# ELN1project.net
KiCad netlist of a schematic drawn in Altium Designer
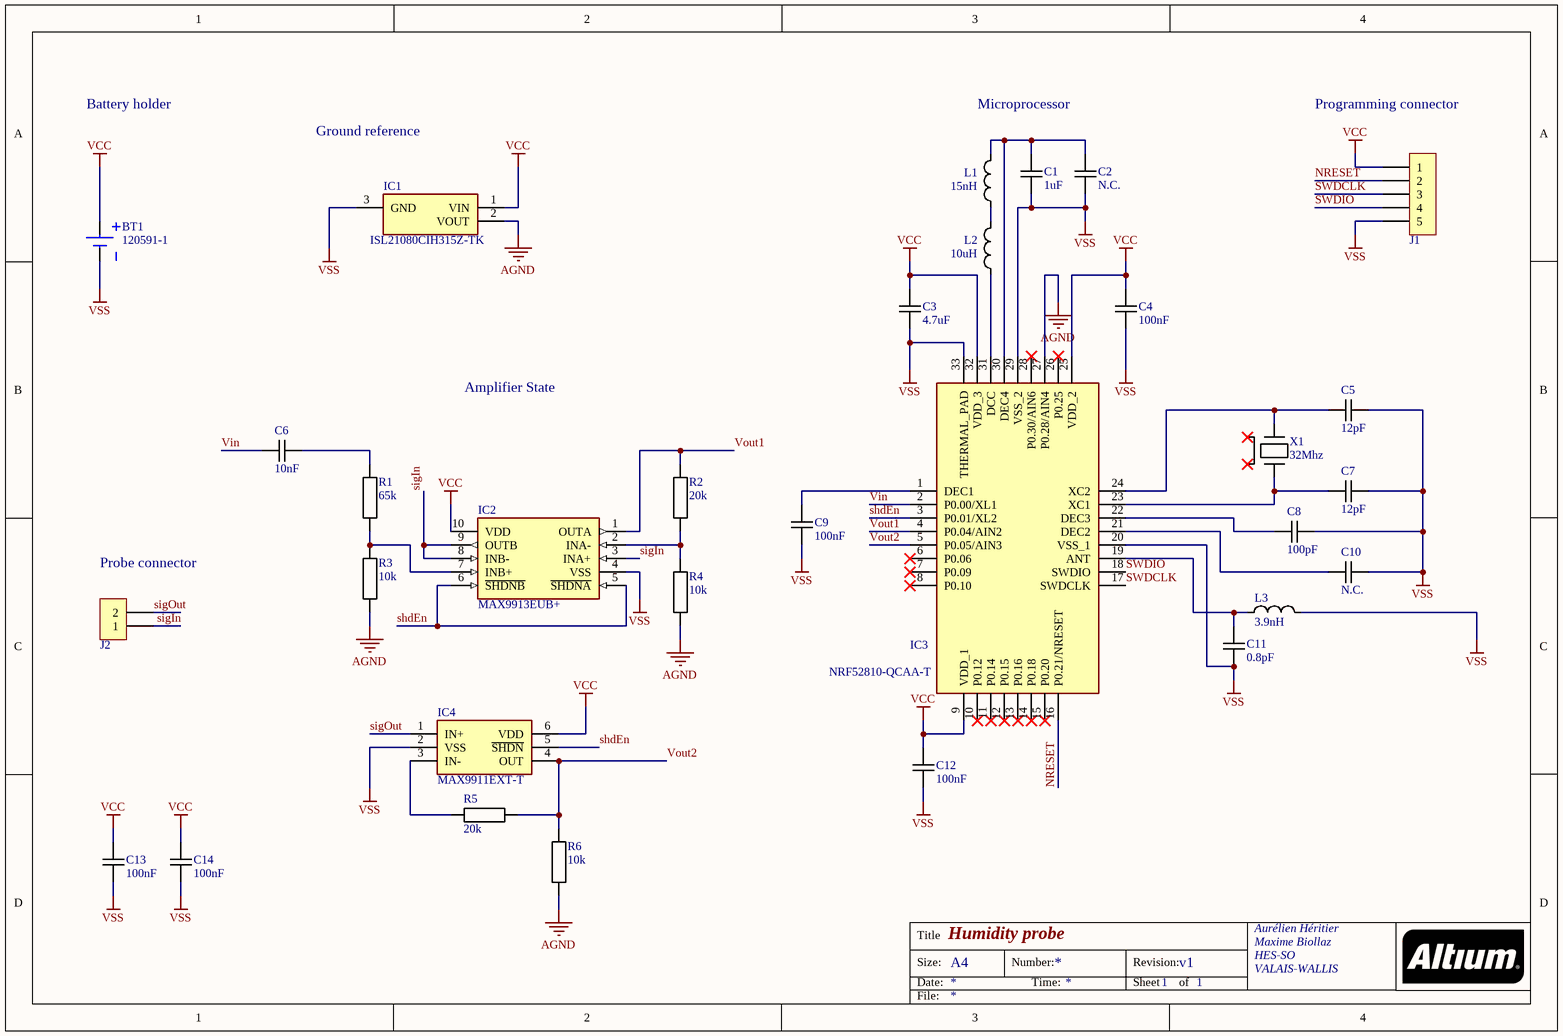
[diagram p0: ELN1project.SchDoc]

(export (version "E")
  (design (tool "Eeschema 10.0.6"))
  (components
    (comp (ref "BT1")
      (value "120591-1")
      (footprint "TECO-120591-1-2_V")
      (description "Lithium Battery Holder for CR2032 3V Cell")
      (fields (field (name "MANUFACTURER") "TE Connectivity"))
      (libsource (lib "TE_Connectivity_120591_1") (part "120591-1"))
    )
    (comp (ref "C1")
      (value "1uF")
      (footprint "CAPACITOR 1005 REFLOW")
      (description "Capacitor")
      (libsource (lib "altium-import") (part "root_1_Capacitor_"))
    )
    (comp (ref "C2")
      (value "N.C.")
      (footprint "CAPACITOR 1005 REFLOW")
      (description "Capacitor")
      (libsource (lib "altium-import") (part "root_1_Capacitor_"))
    )
    (comp (ref "C3")
      (value "4.7uF")
      (footprint "CAPACITOR 1005 REFLOW")
      (description "Capacitor")
      (libsource (lib "altium-import") (part "root_1_Capacitor_"))
    )
    (comp (ref "C4")
      (value "100nF")
      (footprint "CAPACITOR 1005 REFLOW")
      (description "Capacitor")
      (libsource (lib "altium-import") (part "root_1_Capacitor_"))
    )
    (comp (ref "C5")
      (value "12pF")
      (footprint "CAPACITOR 1005 REFLOW")
      (description "Capacitor")
      (libsource (lib "altium-import") (part "root_0_Capacitor_"))
    )
    (comp (ref "C6")
      (value "10nF")
      (footprint "CAPACITOR 1005 REFLOW")
      (description "Capacitor")
      (libsource (lib "altium-import") (part "root_2_Capacitor_"))
    )
    (comp (ref "C7")
      (value "12pF")
      (footprint "CAPACITOR 1005 REFLOW")
      (description "Capacitor")
      (libsource (lib "altium-import") (part "root_0_Capacitor_"))
    )
    (comp (ref "C8")
      (value "100pF")
      (footprint "CAPACITOR 1005 REFLOW")
      (description "Capacitor")
      (libsource (lib "altium-import") (part "root_0_Capacitor_"))
    )
    (comp (ref "C9")
      (value "100nF")
      (footprint "CAPACITOR 1005 REFLOW")
      (description "Capacitor")
      (libsource (lib "altium-import") (part "root_1_Capacitor_"))
    )
    (comp (ref "C10")
      (value "N.C.")
      (footprint "CAPACITOR 1005 REFLOW")
      (description "Capacitor")
      (libsource (lib "altium-import") (part "root_0_Capacitor_"))
    )
    (comp (ref "C11")
      (value "0.8pF")
      (footprint "CAPACITOR 1005 REFLOW")
      (description "Capacitor")
      (libsource (lib "altium-import") (part "root_1_Capacitor_"))
    )
    (comp (ref "C12")
      (value "100nF")
      (footprint "CAPACITOR 1005 REFLOW")
      (description "Capacitor")
      (libsource (lib "altium-import") (part "root_1_Capacitor_"))
    )
    (comp (ref "C13")
      (value "100nF")
      (footprint "CAPACITOR 1005 REFLOW")
      (description "Capacitor")
      (libsource (lib "altium-import") (part "root_1_Capacitor_"))
    )
    (comp (ref "C14")
      (value "100nF")
      (footprint "CAPACITOR 1005 REFLOW")
      (description "Capacitor")
      (libsource (lib "altium-import") (part "root_1_Capacitor_"))
    )
    (comp (ref "IC1")
      (value "ISL21080CIH315Z-TK")
      (footprint "SamacSys:SOT95P237X112-3N")
      (description "Integrated Circuit")
      (fields (field (name "MOUSER PART NUMBER") "968-ISL21080CIH315ZT"))
      (libsource (lib "*") (part "ISL21080CIH315Z-TK"))
    )
    (comp (ref "IC2")
      (value "MAX9913EUB+")
      (footprint "SamacSys:SOP50P490X110-10N")
      (description "Integrated Circuit")
      (libsource (lib "*") (part "MAX9913EUB+"))
    )
    (comp (ref "IC3")
      (value "NRF52810-QCAA-T")
      (footprint "SamacSys:QFN50P500X500X80-33N")
      (description "Integrated Circuit")
      (fields
        (field (name "MOUSER PART NUMBER") "949-NRF52810-QCAA-T")
        (field (name "RS PART NUMBER") "1697120P")
      )
      (libsource (lib "*") (part "NRF52810-QCAA-T"))
    )
    (comp (ref "IC4")
      (value "MAX9911EXT-T")
      (footprint "SamacSys:SOT65P218X110-6N")
      (description "Integrated Circuit")
      (libsource (lib "*") (part "MAX9911EXT-T"))
    )
    (comp (ref "J1")
      (value "*")
      (footprint "PinHeader1x5 P1.27")
      (description "Plug connector")
      (libsource (lib "PinHeader") (part "PinHeader1x5"))
    )
    (comp (ref "J2")
      (value "*")
      (footprint "PinHeader1x2 P1.27")
      (description "Plug connector")
      (libsource (lib "altium-import") (part "root_2_PinHeader1x2_"))
    )
    (comp (ref "L1")
      (value "15nH")
      (footprint "INDUCTOR 1005 REFLOW")
      (description "Inductor")
      (libsource (lib "altium-import") (part "root_1_Inductor_"))
    )
    (comp (ref "L2")
      (value "10uH")
      (footprint "INDUCTOR 1005 REFLOW")
      (description "Inductor")
      (libsource (lib "altium-import") (part "root_1_Inductor_"))
    )
    (comp (ref "L3")
      (value "3.9nH")
      (footprint "INDUCTOR 1005 REFLOW")
      (description "Inductor")
      (libsource (lib "altium-import") (part "root_0_Inductor_"))
    )
    (comp (ref "R1")
      (value "65k")
      (footprint "RESISTOR 0603 REFLOW")
      (description "Resistor")
      (libsource (lib "altium-import") (part "root_1_Resistor_"))
    )
    (comp (ref "R2")
      (value "20k")
      (footprint "RESISTOR 0603 REFLOW")
      (description "Resistor")
      (libsource (lib "altium-import") (part "root_1_Resistor_"))
    )
    (comp (ref "R3")
      (value "10k")
      (footprint "RESISTOR 0603 REFLOW")
      (description "Resistor")
      (libsource (lib "altium-import") (part "root_1_Resistor_"))
    )
    (comp (ref "R4")
      (value "10k")
      (footprint "RESISTOR 0603 REFLOW")
      (description "Resistor")
      (libsource (lib "altium-import") (part "root_1_Resistor_"))
    )
    (comp (ref "R5")
      (value "20k")
      (footprint "RESISTOR 0603 REFLOW")
      (description "Resistor")
      (libsource (lib "altium-import") (part "root_2_Resistor_"))
    )
    (comp (ref "R6")
      (value "10k")
      (footprint "RESISTOR 0603 REFLOW")
      (description "Resistor")
      (libsource (lib "altium-import") (part "root_3_Resistor_"))
    )
    (comp (ref "X1")
      (value "32Mhz")
      (footprint "Crystal C2.0x1.6 Abracon ABM11W")
      (description "Crystal C2.0x1.6 Abracon ABM11W")
      (libsource (lib "altium-import") (part "root_3_Crystal C2.0x1.6 Abracon ABM11W_"))
    )
  )
  (nets
    (net (code "1") (name "/NRESET") (class "Default")
      (node (ref "IC3") (pin "16") (pinfunction "P0.21/NRESET_16") (pintype "passive"))
      (node (ref "J1") (pin "2") (pinfunction "2_2") (pintype "passive"))
    )
    (net (code "2") (name "/SWDCLK") (class "Default")
      (node (ref "IC3") (pin "17") (pinfunction "SWDCLK_17") (pintype "passive"))
      (node (ref "J1") (pin "3") (pinfunction "3_3") (pintype "passive"))
    )
    (net (code "3") (name "/SWDIO") (class "Default")
      (node (ref "IC3") (pin "18") (pinfunction "SWDIO_18") (pintype "passive"))
      (node (ref "J1") (pin "4") (pinfunction "4_4") (pintype "passive"))
    )
    (net (code "4") (name "/Vin") (class "Default")
      (node (ref "C6") (pin "2") (pinfunction "2_2") (pintype "passive"))
      (node (ref "IC3") (pin "2") (pinfunction "P0.00/XL1_2") (pintype "passive"))
    )
    (net (code "5") (name "/Vout1") (class "Default")
      (node (ref "IC2") (pin "1") (pinfunction "OUTA_1") (pintype "output"))
      (node (ref "IC3") (pin "4") (pinfunction "P0.04/AIN2_4") (pintype "passive"))
      (node (ref "R2") (pin "2") (pinfunction "2_2") (pintype "passive"))
    )
    (net (code "6") (name "/Vout2") (class "Default")
      (node (ref "IC3") (pin "5") (pinfunction "P0.05/AIN3_5") (pintype "passive"))
      (node (ref "IC4") (pin "4") (pinfunction "OUT_4") (pintype "passive"))
      (node (ref "R5") (pin "1") (pinfunction "1_1") (pintype "passive"))
      (node (ref "R6") (pin "1") (pinfunction "1_1") (pintype "passive"))
    )
    (net (code "7") (name "/shdEn") (class "Default")
      (node (ref "IC2") (pin "5") (pinfunction "~{SHDNA}_5") (pintype "input"))
      (node (ref "IC2") (pin "6") (pinfunction "~{SHDNB}_6") (pintype "input"))
      (node (ref "IC3") (pin "3") (pinfunction "P0.01/XL2_3") (pintype "passive"))
      (node (ref "IC4") (pin "5") (pinfunction "~{SHDN}_5") (pintype "passive"))
    )
    (net (code "8") (name "/sigIn") (class "Default")
      (node (ref "IC2") (pin "3") (pinfunction "INA+_3") (pintype "input"))
      (node (ref "IC2") (pin "8") (pinfunction "INB-_8") (pintype "input"))
      (node (ref "IC2") (pin "9") (pinfunction "OUTB_9") (pintype "output"))
      (node (ref "J2") (pin "1") (pinfunction "1_1") (pintype "passive"))
    )
    (net (code "9") (name "/sigOut") (class "Default")
      (node (ref "IC4") (pin "1") (pinfunction "IN+_1") (pintype "passive"))
      (node (ref "J2") (pin "2") (pinfunction "2_2") (pintype "passive"))
    )
    (net (code "10") (name "AGND") (class "Default")
      (node (ref "IC1") (pin "2") (pinfunction "VOUT_2") (pintype "passive"))
      (node (ref "IC3") (pin "27") (pinfunction "P0.28/AIN4_27") (pintype "passive"))
      (node (ref "R3") (pin "1") (pinfunction "1_1") (pintype "passive"))
      (node (ref "R4") (pin "1") (pinfunction "1_1") (pintype "passive"))
      (node (ref "R6") (pin "2") (pinfunction "2_2") (pintype "passive"))
    )
    (net (code "11") (name "Net-(C6-Pad1)") (class "Default")
      (node (ref "C6") (pin "1") (pinfunction "1_1") (pintype "passive"))
      (node (ref "R1") (pin "2") (pinfunction "2_2") (pintype "passive"))
    )
    (net (code "12") (name "Net-(IC2-INA-)") (class "Default")
      (node (ref "IC2") (pin "2") (pinfunction "INA-_2") (pintype "input"))
      (node (ref "R2") (pin "1") (pinfunction "1_1") (pintype "passive"))
      (node (ref "R4") (pin "2") (pinfunction "2_2") (pintype "passive"))
    )
    (net (code "13") (name "Net-(IC2-INB+)") (class "Default")
      (node (ref "IC2") (pin "7") (pinfunction "INB+_7") (pintype "input"))
      (node (ref "R1") (pin "1") (pinfunction "1_1") (pintype "passive"))
      (node (ref "R3") (pin "2") (pinfunction "2_2") (pintype "passive"))
    )
    (net (code "14") (name "Net-(IC3-ANT)") (class "Default")
      (node (ref "C11") (pin "2") (pinfunction "2_2") (pintype "passive"))
      (node (ref "IC3") (pin "19") (pinfunction "ANT_19") (pintype "passive"))
      (node (ref "L3") (pin "1") (pinfunction "1_1") (pintype "passive"))
    )
    (net (code "15") (name "Net-(IC3-DCC)") (class "Default")
      (node (ref "IC3") (pin "31") (pinfunction "DCC_31") (pintype "passive"))
      (node (ref "L2") (pin "1") (pinfunction "1_1") (pintype "passive"))
    )
    (net (code "16") (name "Net-(IC3-DEC1)") (class "Default")
      (node (ref "C9") (pin "2") (pinfunction "2_2") (pintype "passive"))
      (node (ref "IC3") (pin "1") (pinfunction "DEC1_1") (pintype "passive"))
    )
    (net (code "17") (name "Net-(IC3-DEC2)") (class "Default")
      (node (ref "C10") (pin "1") (pinfunction "1_1") (pintype "passive"))
      (node (ref "IC3") (pin "21") (pinfunction "DEC2_21") (pintype "passive"))
    )
    (net (code "18") (name "Net-(IC3-DEC3)") (class "Default")
      (node (ref "C8") (pin "1") (pinfunction "1_1") (pintype "passive"))
      (node (ref "IC3") (pin "22") (pinfunction "DEC3_22") (pintype "passive"))
    )
    (net (code "19") (name "Net-(IC3-DEC4)") (class "Default")
      (node (ref "C1") (pin "2") (pinfunction "2_2") (pintype "passive"))
      (node (ref "C2") (pin "2") (pinfunction "2_2") (pintype "passive"))
      (node (ref "IC3") (pin "30") (pinfunction "DEC4_30") (pintype "passive"))
      (node (ref "L1") (pin "2") (pinfunction "2_2") (pintype "passive"))
    )
    (net (code "20") (name "Net-(IC3-XC1)") (class "Default")
      (node (ref "C7") (pin "1") (pinfunction "1_1") (pintype "passive"))
      (node (ref "IC3") (pin "23") (pinfunction "XC1_23") (pintype "passive"))
      (node (ref "X1") (pin "3") (pinfunction "3_3") (pintype "passive"))
    )
    (net (code "21") (name "Net-(IC3-XC2)") (class "Default")
      (node (ref "C5") (pin "1") (pinfunction "1_1") (pintype "passive"))
      (node (ref "IC3") (pin "24") (pinfunction "XC2_24") (pintype "passive"))
      (node (ref "X1") (pin "1") (pinfunction "1_1") (pintype "passive"))
    )
    (net (code "22") (name "Net-(IC4-IN-)") (class "Default")
      (node (ref "IC4") (pin "3") (pinfunction "IN-_3") (pintype "passive"))
      (node (ref "R5") (pin "2") (pinfunction "2_2") (pintype "passive"))
    )
    (net (code "23") (name "Net-(L1-Pad1)") (class "Default")
      (node (ref "L1") (pin "1") (pinfunction "1_1") (pintype "passive"))
      (node (ref "L2") (pin "2") (pinfunction "2_2") (pintype "passive"))
    )
    (net (code "24") (name "VCC") (class "Default")
      (node (ref "BT1") (pin "1") (pinfunction "+_1") (pintype "passive"))
      (node (ref "C12") (pin "2") (pinfunction "2_2") (pintype "passive"))
      (node (ref "C13") (pin "2") (pinfunction "2_2") (pintype "passive"))
      (node (ref "C14") (pin "2") (pinfunction "2_2") (pintype "passive"))
      (node (ref "C3") (pin "2") (pinfunction "2_2") (pintype "passive"))
      (node (ref "C4") (pin "2") (pinfunction "2_2") (pintype "passive"))
      (node (ref "IC1") (pin "1") (pinfunction "VIN_1") (pintype "passive"))
      (node (ref "IC2") (pin "10") (pinfunction "VDD_10") (pintype "power_in"))
      (node (ref "IC3") (pin "25") (pinfunction "VDD_2_25") (pintype "passive"))
      (node (ref "IC3") (pin "32") (pinfunction "VDD_3_32") (pintype "passive"))
      (node (ref "IC3") (pin "9") (pinfunction "VDD_1_9") (pintype "passive"))
      (node (ref "IC4") (pin "6") (pinfunction "VDD_6") (pintype "passive"))
      (node (ref "J1") (pin "1") (pinfunction "1_1") (pintype "passive"))
    )
    (net (code "25") (name "VSS") (class "Default")
      (node (ref "BT1") (pin "2") (pinfunction "-_2") (pintype "passive"))
      (node (ref "C1") (pin "1") (pinfunction "1_1") (pintype "passive"))
      (node (ref "C10") (pin "2") (pinfunction "2_2") (pintype "passive"))
      (node (ref "C11") (pin "1") (pinfunction "1_1") (pintype "passive"))
      (node (ref "C12") (pin "1") (pinfunction "1_1") (pintype "passive"))
      (node (ref "C13") (pin "1") (pinfunction "1_1") (pintype "passive"))
      (node (ref "C14") (pin "1") (pinfunction "1_1") (pintype "passive"))
      (node (ref "C2") (pin "1") (pinfunction "1_1") (pintype "passive"))
      (node (ref "C3") (pin "1") (pinfunction "1_1") (pintype "passive"))
      (node (ref "C4") (pin "1") (pinfunction "1_1") (pintype "passive"))
      (node (ref "C5") (pin "2") (pinfunction "2_2") (pintype "passive"))
      (node (ref "C7") (pin "2") (pinfunction "2_2") (pintype "passive"))
      (node (ref "C8") (pin "2") (pinfunction "2_2") (pintype "passive"))
      (node (ref "C9") (pin "1") (pinfunction "1_1") (pintype "passive"))
      (node (ref "IC1") (pin "3") (pinfunction "GND_3") (pintype "passive"))
      (node (ref "IC2") (pin "4") (pinfunction "VSS_4") (pintype "power_in"))
      (node (ref "IC3") (pin "20") (pinfunction "VSS_1_20") (pintype "passive"))
      (node (ref "IC3") (pin "29") (pinfunction "VSS_2_29") (pintype "passive"))
      (node (ref "IC3") (pin "33") (pinfunction "THERMAL_PAD_33") (pintype "passive"))
      (node (ref "IC4") (pin "2") (pinfunction "VSS_2") (pintype "passive"))
      (node (ref "J1") (pin "5") (pinfunction "5_5") (pintype "passive"))
      (node (ref "L3") (pin "2") (pinfunction "2_2") (pintype "passive"))
    )
    (net (code "26") (name "unconnected-(IC3-P0.06-Pad6)") (class "Default")
      (node (ref "IC3") (pin "6") (pinfunction "P0.06_6") (pintype "passive+no_connect"))
    )
    (net (code "27") (name "unconnected-(IC3-P0.09-Pad7)") (class "Default")
      (node (ref "IC3") (pin "7") (pinfunction "P0.09_7") (pintype "passive+no_connect"))
    )
    (net (code "28") (name "unconnected-(IC3-P0.10-Pad8)") (class "Default")
      (node (ref "IC3") (pin "8") (pinfunction "P0.10_8") (pintype "passive+no_connect"))
    )
    (net (code "29") (name "unconnected-(IC3-P0.12-Pad10)") (class "Default")
      (node (ref "IC3") (pin "10") (pinfunction "P0.12_10") (pintype "passive+no_connect"))
    )
    (net (code "30") (name "unconnected-(IC3-P0.14-Pad11)") (class "Default")
      (node (ref "IC3") (pin "11") (pinfunction "P0.14_11") (pintype "passive+no_connect"))
    )
    (net (code "31") (name "unconnected-(IC3-P0.15-Pad12)") (class "Default")
      (node (ref "IC3") (pin "12") (pinfunction "P0.15_12") (pintype "passive+no_connect"))
    )
    (net (code "32") (name "unconnected-(IC3-P0.16-Pad13)") (class "Default")
      (node (ref "IC3") (pin "13") (pinfunction "P0.16_13") (pintype "passive+no_connect"))
    )
    (net (code "33") (name "unconnected-(IC3-P0.18-Pad14)") (class "Default")
      (node (ref "IC3") (pin "14") (pinfunction "P0.18_14") (pintype "passive+no_connect"))
    )
    (net (code "34") (name "unconnected-(IC3-P0.20-Pad15)") (class "Default")
      (node (ref "IC3") (pin "15") (pinfunction "P0.20_15") (pintype "passive+no_connect"))
    )
    (net (code "35") (name "unconnected-(IC3-P0.25-Pad26)") (class "Default")
      (node (ref "IC3") (pin "26") (pinfunction "P0.25_26") (pintype "passive+no_connect"))
    )
    (net (code "36") (name "unconnected-(IC3-P0.30{slash}AIN6-Pad28)") (class "Default")
      (node (ref "IC3") (pin "28") (pinfunction "P0.30/AIN6_28") (pintype "passive+no_connect"))
    )
    (net (code "37") (name "unconnected-(X1-Pad2)") (class "Default")
      (node (ref "X1") (pin "2") (pinfunction "2_2") (pintype "passive+no_connect"))
    )
    (net (code "38") (name "unconnected-(X1-Pad4)") (class "Default")
      (node (ref "X1") (pin "4") (pinfunction "4_4") (pintype "passive+no_connect"))
    )
  )
)
